# Level_Shifter.net
KiCad netlist of a schematic drawn in Altium Designer
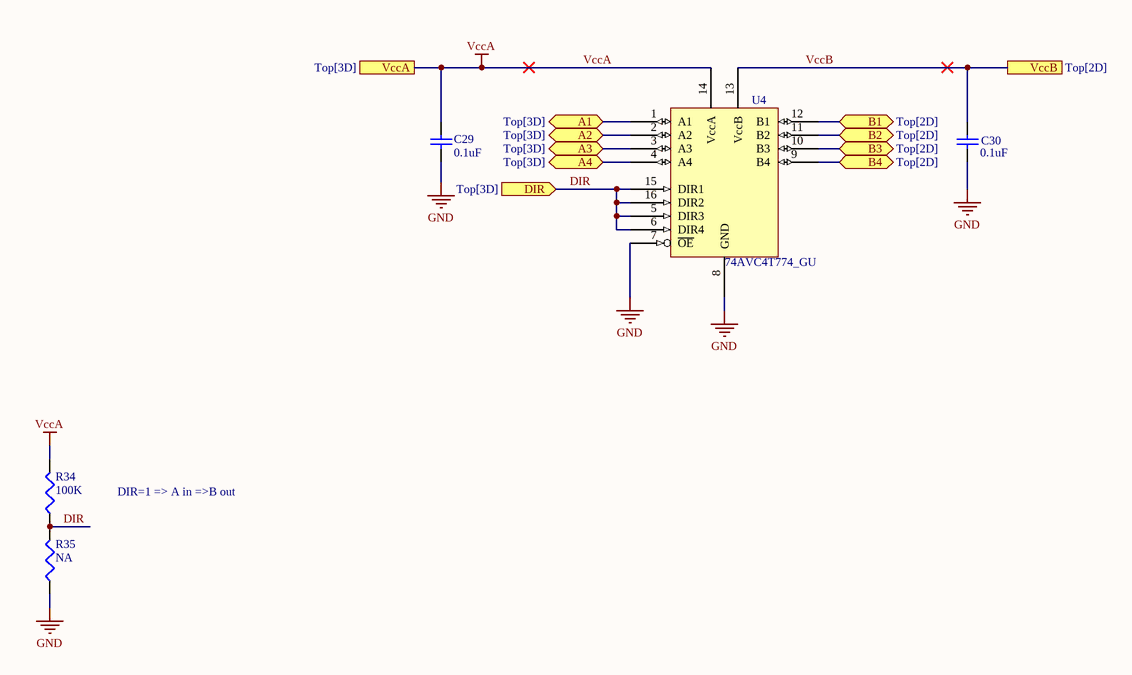
[diagram p0: Level Shifter.SchDoc]

(export (version "E")
  (design (tool "Eeschema 10.0.6"))
  (components
    (comp (ref "C29")
      (value "0.1uF 50V")
      (footprint "C0402")
      (description "CAP CER 0.1uF 50V NP0 0402")
      (fields
        (field (name "MANUFACTURER PART NUMBER") "C1005C0G1H6R8D")
        (field (name "MANUFACTURER") "TDK Corporation")
        (field (name "CAPACITANCE") "0.1uF")
      )
      (libsource (lib "L_SCH_C") (part "CAP CER 6.8pF 50V NP0 0402"))
    )
    (comp (ref "C30")
      (value "0.1uF 50V")
      (footprint "C0402")
      (description "CAP CER 0.1uF 50V NP0 0402")
      (fields
        (field (name "MANUFACTURER PART NUMBER") "C1005C0G1H6R8D")
        (field (name "MANUFACTURER") "TDK Corporation")
        (field (name "CAPACITANCE") "0.1uF")
      )
      (libsource (lib "L_SCH_C") (part "CAP CER 6.8pF 50V NP0 0402"))
    )
    (comp (ref "R34")
      (value "100K")
      (footprint "R0402")
      (description "RES 100K OHM 1/16W 1% 0402")
      (fields
        (field (name "MANUFACTURER PART NUMBER") "RMCF0402FT3K09")
        (field (name "MANUFACTURER") "Stackpole Electronics Inc")
      )
      (libsource (lib "L_SCH_R") (part "RES 3.09K OHM 1/16W 1% 0402"))
    )
    (comp (ref "R35")
      (value "NA")
      (footprint "R0402")
      (description "RES 3.09K OHM 1/16W 1% 0402")
      (fields
        (field (name "MANUFACTURER PART NUMBER") "RMCF0402FT3K09")
        (field (name "MANUFACTURER") "Stackpole Electronics Inc")
      )
      (libsource (lib "L_SCH_R") (part "RES 3.09K OHM 1/16W 1% 0402"))
    )
    (comp (ref "U4")
      (value "74AVC4T774_GU")
      (footprint "NXP_74AVC4T245GU,115")
      (libsource (lib "74AVC4T774_GU") (part "74AVC4T774_GU"))
    )
  )
  (nets
    (net (code "1") (name "/A1") (class "Default")
      (node (ref "U4") (pin "1") (pinfunction "A1_1") (pintype "bidirectional"))
    )
    (net (code "2") (name "/A2") (class "Default")
      (node (ref "U4") (pin "2") (pinfunction "A2_2") (pintype "bidirectional"))
    )
    (net (code "3") (name "/A3") (class "Default")
      (node (ref "U4") (pin "3") (pinfunction "A3_3") (pintype "bidirectional"))
    )
    (net (code "4") (name "/A4") (class "Default")
      (node (ref "U4") (pin "4") (pinfunction "A4_4") (pintype "bidirectional"))
    )
    (net (code "5") (name "/B1") (class "Default")
      (node (ref "U4") (pin "12") (pinfunction "B1_12") (pintype "bidirectional"))
    )
    (net (code "6") (name "/B2") (class "Default")
      (node (ref "U4") (pin "11") (pinfunction "B2_11") (pintype "bidirectional"))
    )
    (net (code "7") (name "/B3") (class "Default")
      (node (ref "U4") (pin "10") (pinfunction "B3_10") (pintype "bidirectional"))
    )
    (net (code "8") (name "/B4") (class "Default")
      (node (ref "U4") (pin "9") (pinfunction "B4_9") (pintype "bidirectional"))
    )
    (net (code "9") (name "/DIR") (class "Default")
      (node (ref "R34") (pin "1") (pinfunction "1_1") (pintype "passive"))
      (node (ref "R35") (pin "2") (pinfunction "2_2") (pintype "passive"))
      (node (ref "U4") (pin "15") (pinfunction "DIR1_15") (pintype "input"))
      (node (ref "U4") (pin "16") (pinfunction "DIR2_16") (pintype "input"))
      (node (ref "U4") (pin "5") (pinfunction "DIR3_5") (pintype "input"))
      (node (ref "U4") (pin "6") (pinfunction "DIR4_6") (pintype "input"))
    )
    (net (code "10") (name "/VccB") (class "Default")
      (node (ref "C30") (pin "2") (pinfunction "2_2") (pintype "passive"))
      (node (ref "U4") (pin "13") (pinfunction "VccB_13") (pintype "power_in"))
    )
    (net (code "11") (name "GND") (class "Default")
      (node (ref "C29") (pin "1") (pinfunction "1_1") (pintype "passive"))
      (node (ref "C30") (pin "1") (pinfunction "1_1") (pintype "passive"))
      (node (ref "R35") (pin "1") (pinfunction "1_1") (pintype "passive"))
      (node (ref "U4") (pin "7") (pinfunction "~{OE}_7") (pintype "input"))
      (node (ref "U4") (pin "8") (pinfunction "GND_8") (pintype "power_in"))
    )
    (net (code "12") (name "VccA") (class "Default")
      (node (ref "C29") (pin "2") (pinfunction "2_2") (pintype "passive"))
      (node (ref "R34") (pin "2") (pinfunction "2_2") (pintype "passive"))
      (node (ref "U4") (pin "14") (pinfunction "VccA_14") (pintype "power_in"))
    )
  )
)
